# SH1-POWER.net
KiCad netlist of a schematic drawn in Altium Designer
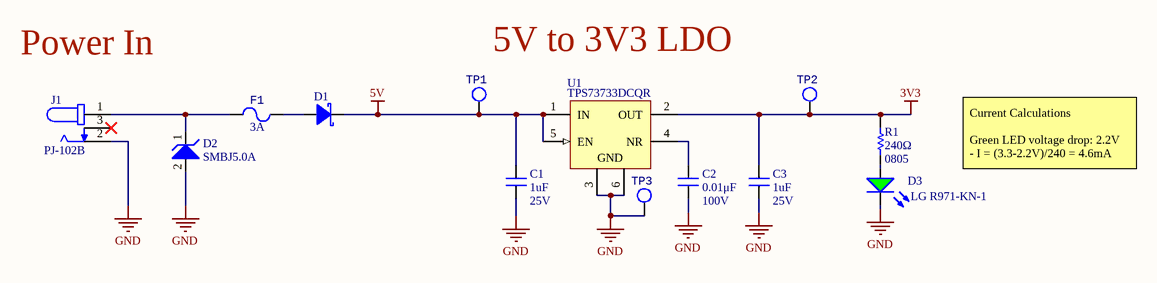
[diagram p0: SH1-POWER.SchDoc]

(export (version "E")
  (design (tool "Eeschema 10.0.6"))
  (components
    (comp (ref "C1")
      (value "~")
      (footprint "CAPC2012X140N")
      (description "CAP CER 1UF 25V X7R 0805")
      (fields
        (field (name "TOLERANCE") "10%")
        (field (name "CAPACITANCE") "1uF")
        (field (name "VOLTAGE RATING (DC)") "25V")
      )
      (libsource (lib "*") (part "CAP_1uF_25V_0805"))
    )
    (comp (ref "C2")
      (value "0.01μF")
      (footprint "CAP2012")
      (description "CAP CER 10000PF 100V X7R 0805")
      (fields
        (field (name "TOLERANCE") "10%")
        (field (name "VOLTAGE RATING") "100V")
        (field (name "Comment") "CAP_0.01uF_100V_0805")
      )
      (libsource (lib "UWRT_Schematic_Library_2020") (part "CAP_0.01uF_100V_0805"))
    )
    (comp (ref "C3")
      (value "~")
      (footprint "CAPC2012X140N")
      (description "CAP CER 1UF 25V X7R 0805")
      (fields
        (field (name "TOLERANCE") "10%")
        (field (name "CAPACITANCE") "1uF")
        (field (name "VOLTAGE RATING (DC)") "25V")
      )
      (libsource (lib "*") (part "CAP_1uF_25V_0805"))
    )
    (comp (ref "D1")
      (value "DIO_SCHOTTKY_30V_2A")
      (footprint "SOD-128")
      (description "DIODE SCHOTTKY 30V 2A PMDTM")
      (libsource (lib "UWRT_Schematic_Library_2020") (part "DIO_SCHOTTKY_30V_2A"))
    )
    (comp (ref "D2")
      (value "TVS_DIODE_UNIDIR_5V")
      (footprint "SMBJ5.0A")
      (description "TVS DIODE 5V 9.2V DO214AA")
      (fields (field (name "MANUFACTURER PART NUMBER 1") "SMBJ5.0A"))
      (libsource (lib "UWRT_Schematic_Library_2020") (part "TVS_DIODE_UNIDIR_5V"))
    )
    (comp (ref "D3")
      (value "LG R971-KN-1")
      (footprint "LED_0805_LINE")
      (description "LED GREEN DIFFUSED 0805 SMD")
      (libsource (lib "UWRT_Schematic_Library_2020") (part "DIO_LED_G"))
    )
    (comp (ref "F1")
      (value "FUSE_3A_1206")
      (footprint "FUSE_1206")
      (description "FUSE SMD 3A 32V 1206")
      (fields (field (name "CURRENT RATING") "3A"))
      (libsource (lib "UWRT_Schematic_Library_2020") (part "FUSE_3A_1206"))
    )
    (comp (ref "J1")
      (value "PJ-102B")
      (footprint "CUI_PJ-102B")
      (description "CONN PWR JACK 2.5X5.5MM SOLDER")
      (libsource (lib "UWRT_Schematic_Library_2020") (part "PJ-102B"))
    )
    (comp (ref "R1")
      (value "240")
      (footprint "RESC2012X60N")
      (description "RES 240 OHM 1% 1/8W 0805")
      (fields
        (field (name "TOLERANCE") "1%")
        (field (name "RESISTANCE") "240Ω")
        (field (name "CASE CODE (IMPERIAL)") "0805")
      )
      (libsource (lib "UWRT_Schematic_Library_2020") (part "RES_240Ω_0805_1%"))
    )
    (comp (ref "TP1")
      (value "TESTPOINT_LOOP")
      (footprint "TESTPOINT_LOOP")
      (description "Loop testpoint through-hole pad")
      (libsource (lib "UWRT_Schematic_Library_2020") (part "TESTPOINT_LOOP"))
    )
    (comp (ref "TP2")
      (value "TESTPOINT_LOOP")
      (footprint "TESTPOINT_LOOP")
      (description "Loop testpoint through-hole pad")
      (libsource (lib "UWRT_Schematic_Library_2020") (part "TESTPOINT_LOOP"))
    )
    (comp (ref "TP3")
      (value "TESTPOINT_LOOP")
      (footprint "TESTPOINT_LOOP")
      (description "Loop testpoint through-hole pad")
      (libsource (lib "UWRT_Schematic_Library_2020") (part "TESTPOINT_LOOP"))
    )
    (comp (ref "U1")
      (value "TPS73733DCQR")
      (footprint "UWRT_Footprint_Library_2020:SOT-223-6")
      (description "IC REG LINEAR 3.3V 1A SOT223-6")
      (fields (field (name "MANUFACTURER") "Texas Instruments"))
      (libsource (lib "Altium Content Vault") (part "LDO_3.3V_1A"))
    )
  )
  (nets
    (net (code "1") (name "3V3") (class "Default")
      (node (ref "C3") (pin "2") (pinfunction "2_2") (pintype "passive"))
      (node (ref "R1") (pin "2") (pinfunction "2_2") (pintype "passive"))
      (node (ref "TP2") (pin "1") (pintype "passive"))
      (node (ref "U1") (pin "2") (pinfunction "OUT_2") (pintype "power_in"))
    )
    (net (code "2") (name "5V") (class "Default")
      (node (ref "C1") (pin "1") (pinfunction "1_1") (pintype "passive"))
      (node (ref "D1") (pin "2") (pinfunction "Cathode_2") (pintype "passive"))
      (node (ref "TP1") (pin "1") (pintype "passive"))
      (node (ref "U1") (pin "1") (pinfunction "IN_1") (pintype "power_in"))
      (node (ref "U1") (pin "5") (pinfunction "EN_5") (pintype "input"))
    )
    (net (code "3") (name "GND") (class "Default")
      (node (ref "C1") (pin "2") (pinfunction "2_2") (pintype "passive"))
      (node (ref "C2") (pin "1") (pinfunction "1_1") (pintype "passive"))
      (node (ref "C3") (pin "1") (pinfunction "1_1") (pintype "passive"))
      (node (ref "D2") (pin "2") (pinfunction "2_2") (pintype "passive"))
      (node (ref "D3") (pin "2") (pinfunction "K_2") (pintype "passive"))
      (node (ref "J1") (pin "2") (pinfunction "2_2") (pintype "passive"))
      (node (ref "TP3") (pin "1") (pintype "passive"))
      (node (ref "U1") (pin "3") (pinfunction "GND_3") (pintype "power_in"))
      (node (ref "U1") (pin "6") (pinfunction "GND_6") (pintype "power_in"))
    )
    (net (code "4") (name "Net-(D1-Anode)") (class "Default")
      (node (ref "D1") (pin "1") (pinfunction "Anode_1") (pintype "passive"))
      (node (ref "F1") (pin "2") (pinfunction "2_2") (pintype "passive"))
    )
    (net (code "5") (name "Net-(D2-Pad1)") (class "Default")
      (node (ref "D2") (pin "1") (pinfunction "1_1") (pintype "passive"))
      (node (ref "F1") (pin "1") (pinfunction "1_1") (pintype "passive"))
      (node (ref "J1") (pin "1") (pinfunction "1_1") (pintype "passive"))
    )
    (net (code "6") (name "Net-(D3-A)") (class "Default")
      (node (ref "D3") (pin "1") (pinfunction "A_1") (pintype "passive"))
      (node (ref "R1") (pin "1") (pinfunction "1_1") (pintype "passive"))
    )
    (net (code "7") (name "Net-(U1-NR)") (class "Default")
      (node (ref "C2") (pin "2") (pinfunction "2_2") (pintype "passive"))
      (node (ref "U1") (pin "4") (pinfunction "NR_4") (pintype "passive"))
    )
    (net (code "8") (name "unconnected-(J1-Pad3)") (class "Default")
      (node (ref "J1") (pin "3") (pinfunction "3_3") (pintype "passive+no_connect"))
    )
  )
)
